# Transceivers.net
KiCad netlist of a schematic drawn in Altium Designer
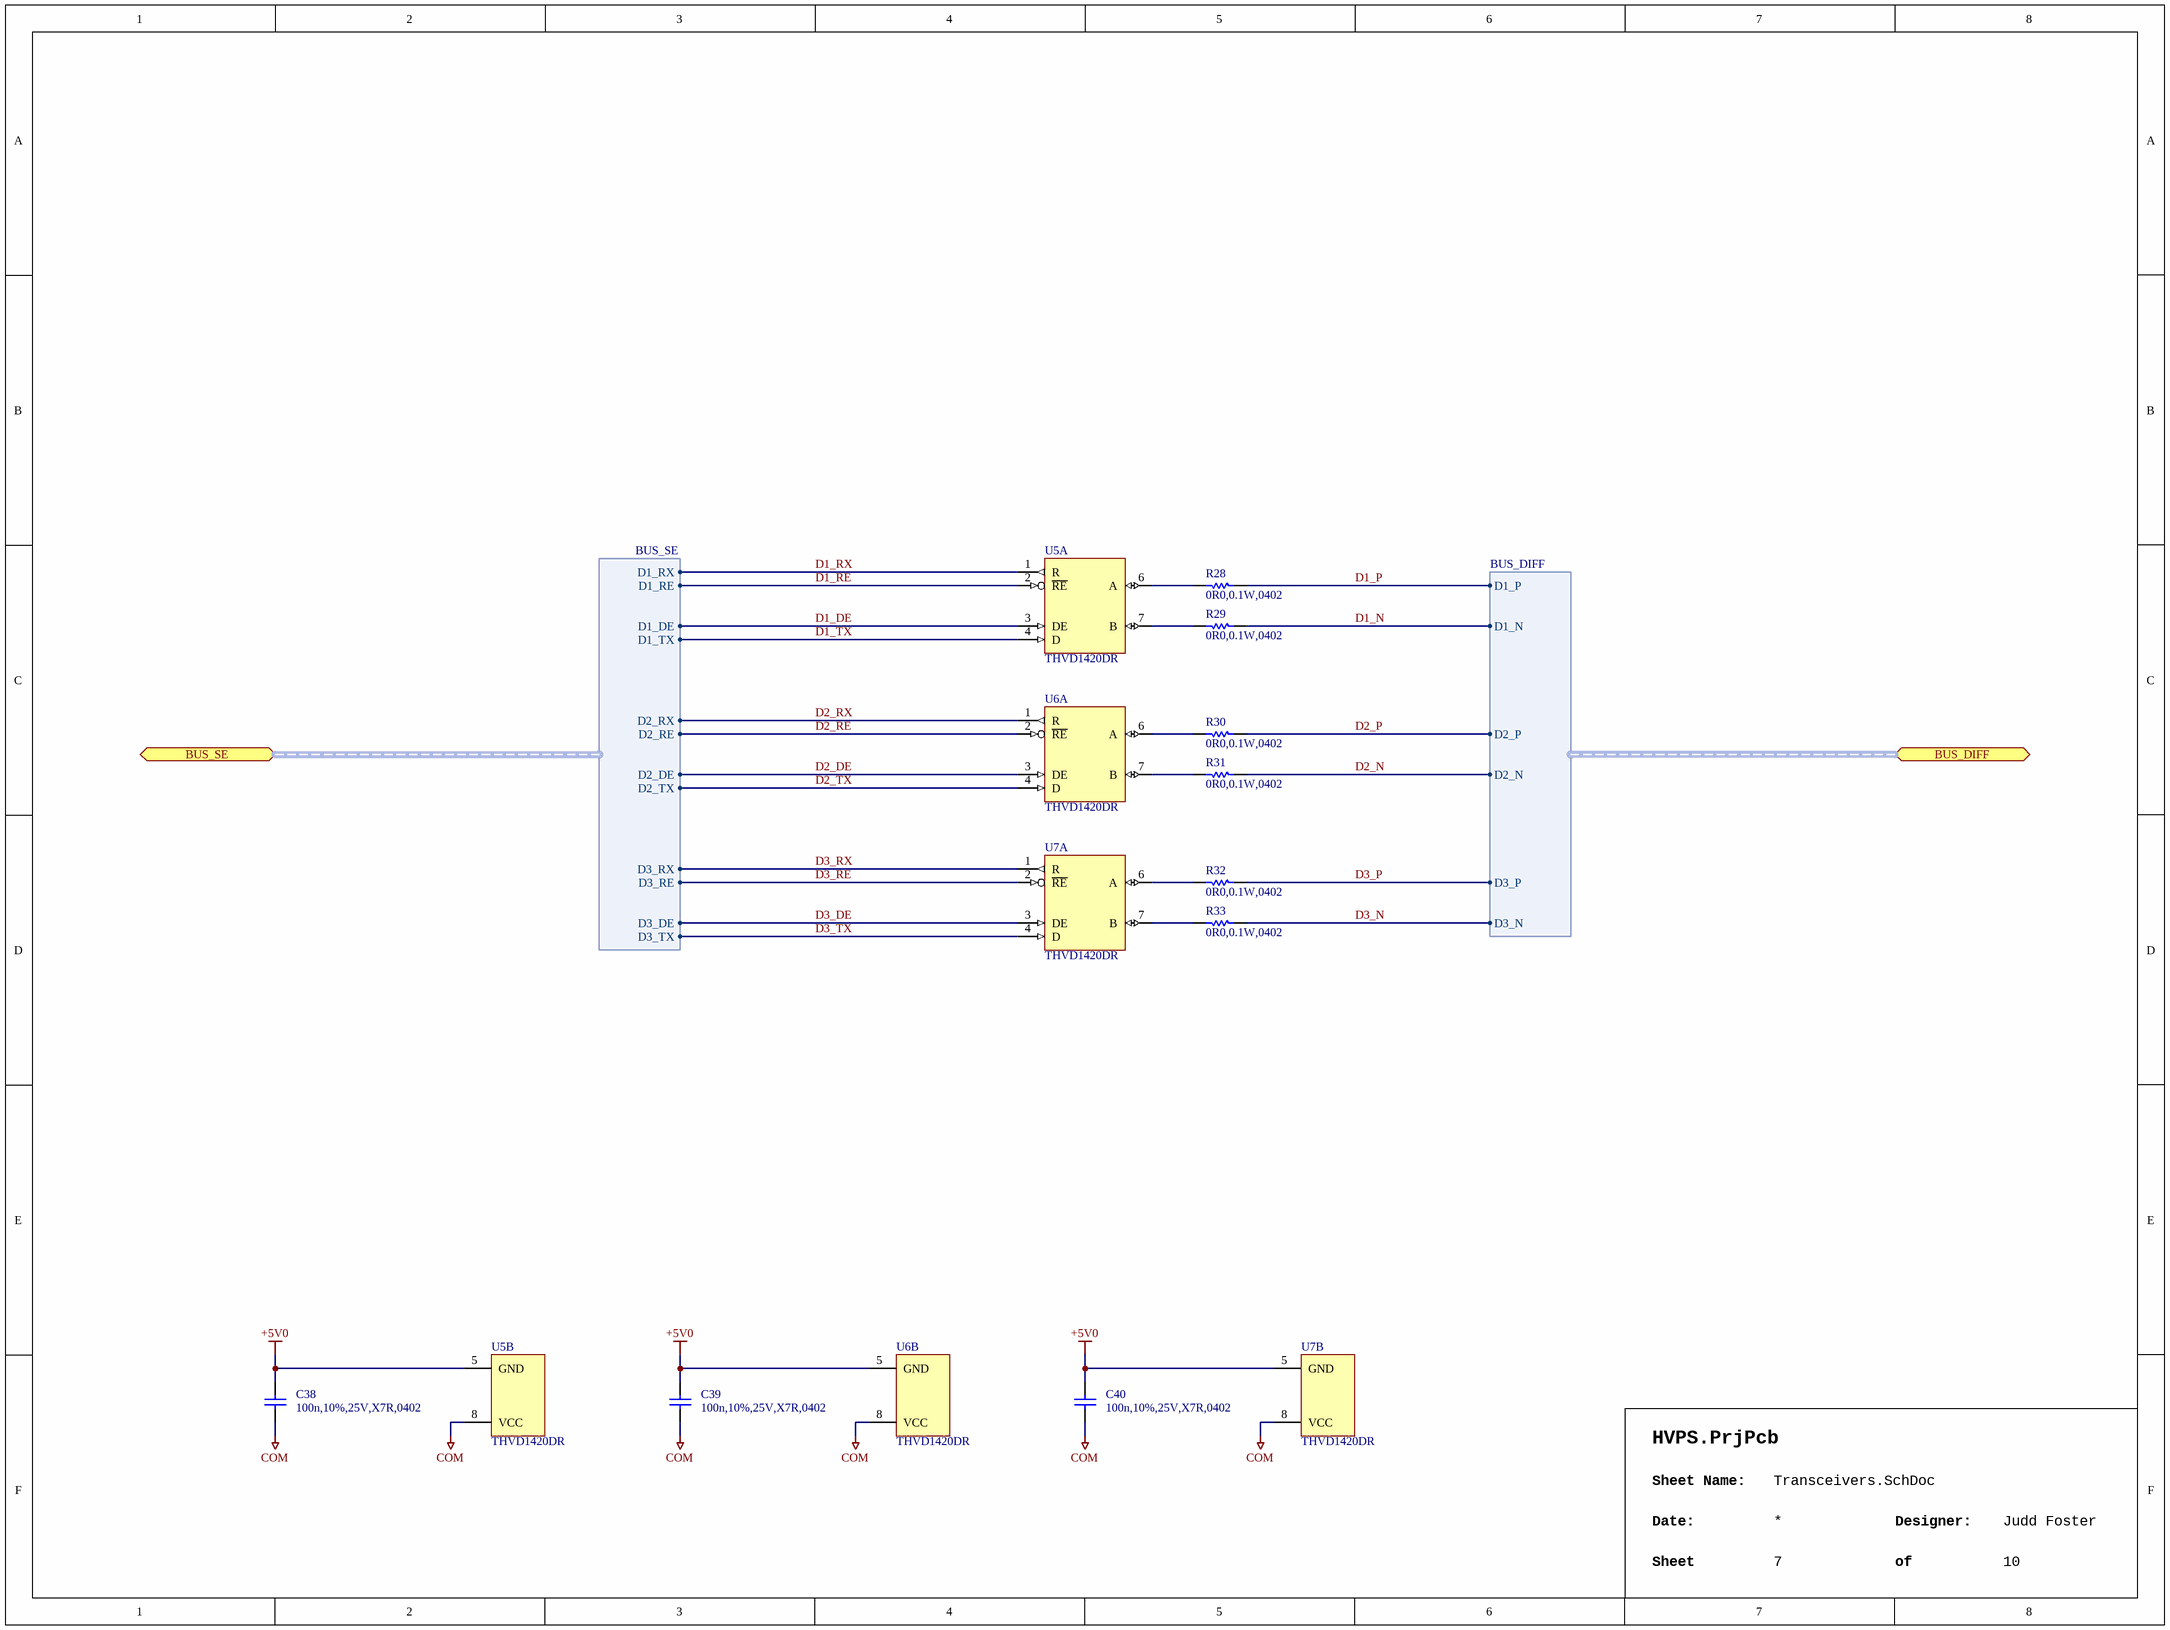
[diagram p0: Transceivers.SchDoc]

(export (version "E")
  (design (tool "Eeschema 10.0.6"))
  (components
    (comp (ref "C38")
      (value "100n,10%,25V,X7R,0402")
      (footprint "CAPC1005X06N")
      (description "0.1ï¿½F ï¿½10% 25V Ceramic Capacitor X7R 0402 (1005 Metric)")
      (fields
        (field (name "MANUFACTURER 1 PART NUMBER") "GRM155R71E104KE14J")
        (field (name "VENDOR 1 PART NUMBER") "490-14603-1-ND")
        (field (name "CREATEDBY") "Judd Foster")
      )
      (libsource (lib "Component Library") (part "CAP,Cer,100nF,10%,25V,X7R,0402"))
    )
    (comp (ref "C39")
      (value "100n,10%,25V,X7R,0402")
      (footprint "CAPC1005X06N")
      (description "0.1ï¿½F ï¿½10% 25V Ceramic Capacitor X7R 0402 (1005 Metric)")
      (fields
        (field (name "MANUFACTURER 1 PART NUMBER") "GRM155R71E104KE14J")
        (field (name "VENDOR 1 PART NUMBER") "490-14603-1-ND")
        (field (name "CREATEDBY") "Judd Foster")
      )
      (libsource (lib "Component Library") (part "CAP,Cer,100nF,10%,25V,X7R,0402"))
    )
    (comp (ref "C40")
      (value "100n,10%,25V,X7R,0402")
      (footprint "CAPC1005X06N")
      (description "0.1ï¿½F ï¿½10% 25V Ceramic Capacitor X7R 0402 (1005 Metric)")
      (fields
        (field (name "MANUFACTURER 1 PART NUMBER") "GRM155R71E104KE14J")
        (field (name "VENDOR 1 PART NUMBER") "490-14603-1-ND")
        (field (name "CREATEDBY") "Judd Foster")
      )
      (libsource (lib "Component Library") (part "CAP,Cer,100nF,10%,25V,X7R,0402"))
    )
    (comp (ref "R28")
      (value "0R0,0.1W,0402")
      (footprint "RESC1005X04N")
      (description "0 Ohms Jumper 0.1W, 1/10W Chip Resistor 0402 (1005 Metric) Automotive AEC-Q200 Thick Film")
      (fields
        (field (name "MANUFACTURER 1 PART NUMBER") "ERJ-2GE0R00X")
        (field (name "VENDOR 1 PART NUMBER") "P0.0JCT-ND")
        (field (name "CREATEDBY") "Judd Foster")
      )
      (libsource (lib "Component Library") (part "RES,0R0,0.1W,0402"))
    )
    (comp (ref "R29")
      (value "0R0,0.1W,0402")
      (footprint "RESC1005X04N")
      (description "0 Ohms Jumper 0.1W, 1/10W Chip Resistor 0402 (1005 Metric) Automotive AEC-Q200 Thick Film")
      (fields
        (field (name "MANUFACTURER 1 PART NUMBER") "ERJ-2GE0R00X")
        (field (name "VENDOR 1 PART NUMBER") "P0.0JCT-ND")
        (field (name "CREATEDBY") "Judd Foster")
      )
      (libsource (lib "Component Library") (part "RES,0R0,0.1W,0402"))
    )
    (comp (ref "R30")
      (value "0R0,0.1W,0402")
      (footprint "RESC1005X04N")
      (description "0 Ohms Jumper 0.1W, 1/10W Chip Resistor 0402 (1005 Metric) Automotive AEC-Q200 Thick Film")
      (fields
        (field (name "MANUFACTURER 1 PART NUMBER") "ERJ-2GE0R00X")
        (field (name "VENDOR 1 PART NUMBER") "P0.0JCT-ND")
        (field (name "CREATEDBY") "Judd Foster")
      )
      (libsource (lib "Component Library") (part "RES,0R0,0.1W,0402"))
    )
    (comp (ref "R31")
      (value "0R0,0.1W,0402")
      (footprint "RESC1005X04N")
      (description "0 Ohms Jumper 0.1W, 1/10W Chip Resistor 0402 (1005 Metric) Automotive AEC-Q200 Thick Film")
      (fields
        (field (name "MANUFACTURER 1 PART NUMBER") "ERJ-2GE0R00X")
        (field (name "VENDOR 1 PART NUMBER") "P0.0JCT-ND")
        (field (name "CREATEDBY") "Judd Foster")
      )
      (libsource (lib "Component Library") (part "RES,0R0,0.1W,0402"))
    )
    (comp (ref "R32")
      (value "0R0,0.1W,0402")
      (footprint "RESC1005X04N")
      (description "0 Ohms Jumper 0.1W, 1/10W Chip Resistor 0402 (1005 Metric) Automotive AEC-Q200 Thick Film")
      (fields
        (field (name "MANUFACTURER 1 PART NUMBER") "ERJ-2GE0R00X")
        (field (name "VENDOR 1 PART NUMBER") "P0.0JCT-ND")
        (field (name "CREATEDBY") "Judd Foster")
      )
      (libsource (lib "Component Library") (part "RES,0R0,0.1W,0402"))
    )
    (comp (ref "R33")
      (value "0R0,0.1W,0402")
      (footprint "RESC1005X04N")
      (description "0 Ohms Jumper 0.1W, 1/10W Chip Resistor 0402 (1005 Metric) Automotive AEC-Q200 Thick Film")
      (fields
        (field (name "MANUFACTURER 1 PART NUMBER") "ERJ-2GE0R00X")
        (field (name "VENDOR 1 PART NUMBER") "P0.0JCT-ND")
        (field (name "CREATEDBY") "Judd Foster")
      )
      (libsource (lib "Component Library") (part "RES,0R0,0.1W,0402"))
    )
    (comp (ref "U5")
      (value "THVD1420DR")
      (footprint "TEXASINSTRUMENTS_PKG_D0008A")
      (description "1/1 Transceiver Half RS422, RS485 8-SOIC")
      (fields
        (field (name "VENDOR 1 PART NUMBER") "296-THVD1420DRCT-ND")
        (field (name "CREATEDBY") "Judd Foster")
      )
      (libsource (lib "Component Library") (part "THVD1420DR"))
    )
    (comp (ref "U6")
      (value "THVD1420DR")
      (footprint "TEXASINSTRUMENTS_PKG_D0008A")
      (description "1/1 Transceiver Half RS422, RS485 8-SOIC")
      (fields
        (field (name "VENDOR 1 PART NUMBER") "296-THVD1420DRCT-ND")
        (field (name "CREATEDBY") "Judd Foster")
      )
      (libsource (lib "Component Library") (part "THVD1420DR"))
    )
    (comp (ref "U7")
      (value "THVD1420DR")
      (footprint "TEXASINSTRUMENTS_PKG_D0008A")
      (description "1/1 Transceiver Half RS422, RS485 8-SOIC")
      (fields
        (field (name "VENDOR 1 PART NUMBER") "296-THVD1420DRCT-ND")
        (field (name "CREATEDBY") "Judd Foster")
      )
      (libsource (lib "Component Library") (part "THVD1420DR"))
    )
  )
  (nets
    (net (code "3") (name "+5V0") (class "Default")
      (node (ref "C38") (pin "2") (pinfunction "2_2") (pintype "passive"))
      (node (ref "C39") (pin "2") (pinfunction "2_2") (pintype "passive"))
      (node (ref "C40") (pin "2") (pinfunction "2_2") (pintype "passive"))
      (node (ref "U5") (pin "5") (pinfunction "GND_5") (pintype "power_in"))
      (node (ref "U6") (pin "5") (pinfunction "GND_5") (pintype "power_in"))
      (node (ref "U7") (pin "5") (pinfunction "GND_5") (pintype "power_in"))
    )
    (net (code "4") (name "/D1_DE") (class "Default")
      (node (ref "U5") (pin "3") (pinfunction "DE_3") (pintype "input"))
    )
    (net (code "5") (name "/D1_N") (class "Default")
      (node (ref "R29") (pin "1") (pinfunction "1_1") (pintype "passive"))
    )
    (net (code "6") (name "/D1_P") (class "Default")
      (node (ref "R28") (pin "1") (pinfunction "1_1") (pintype "passive"))
    )
    (net (code "7") (name "/D1_RE") (class "Default")
      (node (ref "U5") (pin "2") (pinfunction "~{RE}_2") (pintype "input"))
    )
    (net (code "8") (name "/D1_RX") (class "Default")
      (node (ref "U5") (pin "1") (pinfunction "R_1") (pintype "output"))
    )
    (net (code "9") (name "/D1_TX") (class "Default")
      (node (ref "U5") (pin "4") (pinfunction "D_4") (pintype "input"))
    )
    (net (code "10") (name "/D2_DE") (class "Default")
      (node (ref "U6") (pin "3") (pinfunction "DE_3") (pintype "input"))
    )
    (net (code "11") (name "/D2_N") (class "Default")
      (node (ref "R31") (pin "1") (pinfunction "1_1") (pintype "passive"))
    )
    (net (code "12") (name "/D2_P") (class "Default")
      (node (ref "R30") (pin "1") (pinfunction "1_1") (pintype "passive"))
    )
    (net (code "13") (name "/D2_RE") (class "Default")
      (node (ref "U6") (pin "2") (pinfunction "~{RE}_2") (pintype "input"))
    )
    (net (code "14") (name "/D2_RX") (class "Default")
      (node (ref "U6") (pin "1") (pinfunction "R_1") (pintype "output"))
    )
    (net (code "15") (name "/D2_TX") (class "Default")
      (node (ref "U6") (pin "4") (pinfunction "D_4") (pintype "input"))
    )
    (net (code "16") (name "/D3_DE") (class "Default")
      (node (ref "U7") (pin "3") (pinfunction "DE_3") (pintype "input"))
    )
    (net (code "17") (name "/D3_N") (class "Default")
      (node (ref "R33") (pin "1") (pinfunction "1_1") (pintype "passive"))
    )
    (net (code "18") (name "/D3_P") (class "Default")
      (node (ref "R32") (pin "1") (pinfunction "1_1") (pintype "passive"))
    )
    (net (code "19") (name "/D3_RE") (class "Default")
      (node (ref "U7") (pin "2") (pinfunction "~{RE}_2") (pintype "input"))
    )
    (net (code "20") (name "/D3_RX") (class "Default")
      (node (ref "U7") (pin "1") (pinfunction "R_1") (pintype "output"))
    )
    (net (code "21") (name "/D3_TX") (class "Default")
      (node (ref "U7") (pin "4") (pinfunction "D_4") (pintype "input"))
    )
    (net (code "24") (name "COM") (class "Default")
      (node (ref "C38") (pin "1") (pinfunction "1_1") (pintype "passive"))
      (node (ref "C39") (pin "1") (pinfunction "1_1") (pintype "passive"))
      (node (ref "C40") (pin "1") (pinfunction "1_1") (pintype "passive"))
      (node (ref "U5") (pin "8") (pinfunction "VCC_8") (pintype "power_in"))
      (node (ref "U6") (pin "8") (pinfunction "VCC_8") (pintype "power_in"))
      (node (ref "U7") (pin "8") (pinfunction "VCC_8") (pintype "power_in"))
    )
    (net (code "25") (name "Net-(U5A-A)") (class "Default")
      (node (ref "R28") (pin "2") (pinfunction "2_2") (pintype "passive"))
      (node (ref "U5") (pin "6") (pinfunction "A_6") (pintype "bidirectional"))
    )
    (net (code "26") (name "Net-(U5A-B)") (class "Default")
      (node (ref "R29") (pin "2") (pinfunction "2_2") (pintype "passive"))
      (node (ref "U5") (pin "7") (pinfunction "B_7") (pintype "bidirectional"))
    )
    (net (code "27") (name "Net-(U6A-A)") (class "Default")
      (node (ref "R30") (pin "2") (pinfunction "2_2") (pintype "passive"))
      (node (ref "U6") (pin "6") (pinfunction "A_6") (pintype "bidirectional"))
    )
    (net (code "28") (name "Net-(U6A-B)") (class "Default")
      (node (ref "R31") (pin "2") (pinfunction "2_2") (pintype "passive"))
      (node (ref "U6") (pin "7") (pinfunction "B_7") (pintype "bidirectional"))
    )
    (net (code "29") (name "Net-(U7A-A)") (class "Default")
      (node (ref "R32") (pin "2") (pinfunction "2_2") (pintype "passive"))
      (node (ref "U7") (pin "6") (pinfunction "A_6") (pintype "bidirectional"))
    )
    (net (code "30") (name "Net-(U7A-B)") (class "Default")
      (node (ref "R33") (pin "2") (pinfunction "2_2") (pintype "passive"))
      (node (ref "U7") (pin "7") (pinfunction "B_7") (pintype "bidirectional"))
    )
  )
)
